# uSBasp.net
KiCad netlist of a schematic drawn in EAGLE
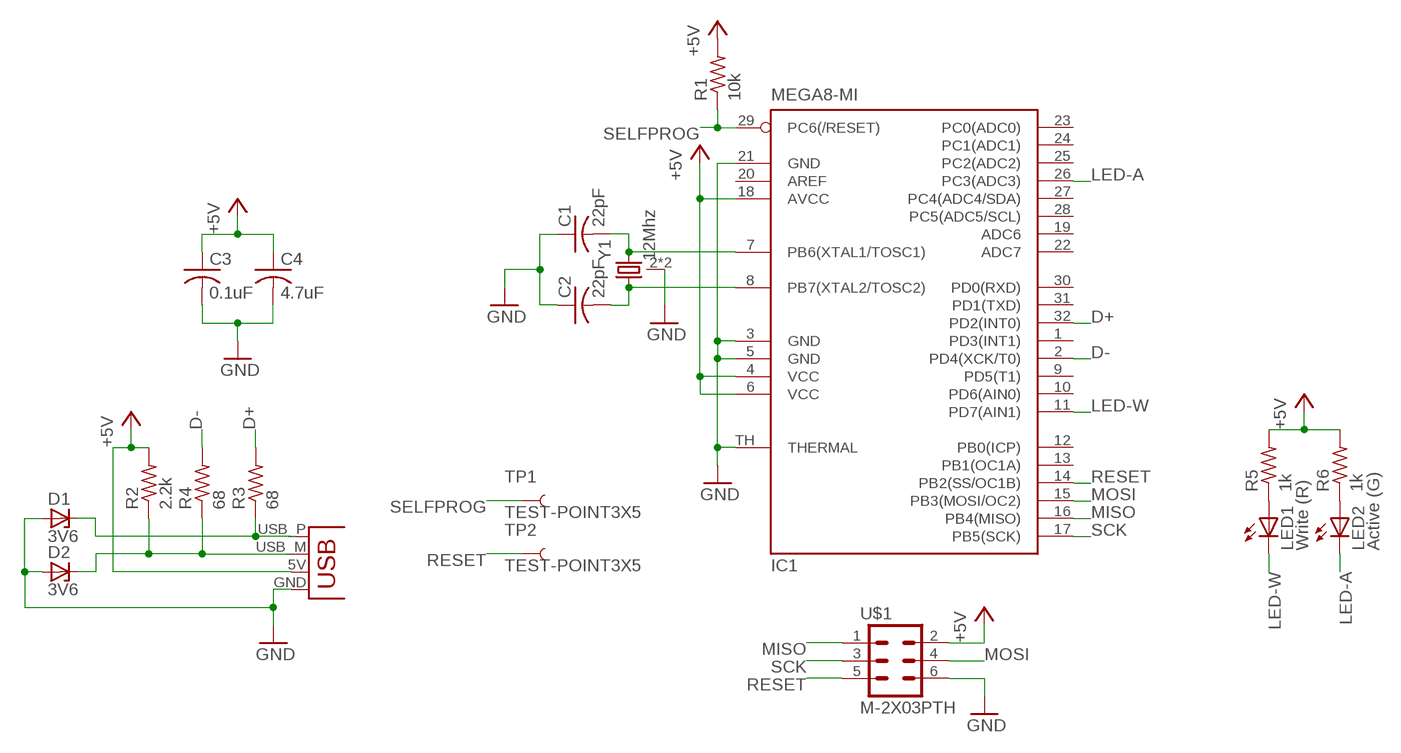
[diagram p0: schematic, sheet 1]

(export (version "E")
  (design (tool "Eeschema 10.0.6"))
  (components
    (comp (ref "C1")
      (value "22pF")
      (footprint "eagle-import:C0402")
      (libsource (lib "eagle-import") (part "C-USC0402"))
    )
    (comp (ref "C2")
      (value "22pF")
      (footprint "eagle-import:C0402")
      (libsource (lib "eagle-import") (part "C-USC0402"))
    )
    (comp (ref "C3")
      (value "0.1uF")
      (footprint "eagle-import:C0402")
      (libsource (lib "eagle-import") (part "C-USC0402"))
    )
    (comp (ref "C4")
      (value "4.7uF")
      (footprint "eagle-import:C0402")
      (libsource (lib "eagle-import") (part "C-USC0402"))
    )
    (comp (ref "D1")
      (value "3V6")
      (footprint "eagle-import:SOT23")
      (libsource (lib "eagle-import") (part "ZENER-DIODESOT23"))
    )
    (comp (ref "D2")
      (value "3V6")
      (footprint "eagle-import:SOT23")
      (libsource (lib "eagle-import") (part "ZENER-DIODESOT23"))
    )
    (comp (ref "IC1")
      (value "MEGA8-MI")
      (footprint "eagle-import:MLF32-TH")
      (fields (field (name "MPN") "ATMEGA88PA-MU"))
      (libsource (lib "eagle-import") (part "MEGA8-MI"))
    )
    (comp (ref "LED1")
      (value "Write (R)")
      (footprint "eagle-import:SML0603")
      (libsource (lib "eagle-import") (part "LEDSML0603"))
    )
    (comp (ref "LED2")
      (value "Active (G)")
      (footprint "eagle-import:SML0603")
      (libsource (lib "eagle-import") (part "LEDSML0603"))
    )
    (comp (ref "R1")
      (value "10k")
      (footprint "eagle-import:R0402")
      (libsource (lib "eagle-import") (part "R-US_R0402"))
    )
    (comp (ref "R2")
      (value "2.2k")
      (footprint "eagle-import:R0402")
      (libsource (lib "eagle-import") (part "R-US_R0402"))
    )
    (comp (ref "R3")
      (value "68")
      (footprint "eagle-import:R0402")
      (libsource (lib "eagle-import") (part "R-US_R0402"))
    )
    (comp (ref "R4")
      (value "68")
      (footprint "eagle-import:R0402")
      (libsource (lib "eagle-import") (part "R-US_R0402"))
    )
    (comp (ref "R5")
      (value "1k")
      (footprint "eagle-import:R0402")
      (libsource (lib "eagle-import") (part "R-US_R0402"))
    )
    (comp (ref "R6")
      (value "1k")
      (footprint "eagle-import:R0402")
      (libsource (lib "eagle-import") (part "R-US_R0402"))
    )
    (comp (ref "TP1")
      (value "TEST-POINT3X5")
      (footprint "eagle-import:PAD.03X.05")
      (libsource (lib "eagle-import") (part "TEST-POINT3X5"))
    )
    (comp (ref "TP2")
      (value "TEST-POINT3X5")
      (footprint "eagle-import:PAD.03X.05")
      (libsource (lib "eagle-import") (part "TEST-POINT3X5"))
    )
    (comp (ref "U$1")
      (value "M-2X03PTH")
      (footprint "eagle-import:M-2X03-0.1-PTH-EDGE")
      (libsource (lib "eagle-import") (part "M-2X03PTH"))
    )
    (comp (ref "X1")
      (value "USBPCB")
      (footprint "eagle-import:USB-A-PCB")
      (libsource (lib "eagle-import") (part "USBPCB"))
    )
    (comp (ref "Y1")
      (value "12Mhz")
      (footprint "eagle-import:CRYSTAL-SMD-3.2X2.5")
      (libsource (lib "eagle-import") (part "CRYSTAL"))
    )
  )
  (nets
    (net (code "1") (name "+5V") (class "Default")
      (node (ref "C3") (pin "1") (pinfunction "1_1") (pintype "passive"))
      (node (ref "C4") (pin "1") (pinfunction "1_1") (pintype "passive"))
      (node (ref "IC1") (pin "18") (pinfunction "AVCC_18") (pintype "power_in"))
      (node (ref "IC1") (pin "4") (pinfunction "VCC_4") (pintype "power_in"))
      (node (ref "IC1") (pin "6") (pinfunction "VCC_6") (pintype "power_in"))
      (node (ref "R1") (pin "2") (pinfunction "2_2") (pintype "passive"))
      (node (ref "R2") (pin "2") (pinfunction "2_2") (pintype "passive"))
      (node (ref "R5") (pin "2") (pinfunction "2_2") (pintype "passive"))
      (node (ref "R6") (pin "2") (pinfunction "2_2") (pintype "passive"))
      (node (ref "U$1") (pin "2") (pinfunction "2_2") (pintype "passive"))
      (node (ref "X1") (pin "5V") (pinfunction "VBUS_5V") (pintype "bidirectional"))
    )
    (net (code "2") (name "/D+") (class "Default")
      (node (ref "IC1") (pin "32") (pinfunction "PD2(INT0)_32") (pintype "bidirectional"))
      (node (ref "R3") (pin "2") (pinfunction "2_2") (pintype "passive"))
    )
    (net (code "3") (name "/D-") (class "Default")
      (node (ref "IC1") (pin "2") (pinfunction "PD4(XCK/T0)_2") (pintype "bidirectional"))
      (node (ref "R4") (pin "2") (pinfunction "2_2") (pintype "passive"))
    )
    (net (code "4") (name "/LED-A") (class "Default")
      (node (ref "IC1") (pin "26") (pinfunction "PC3(ADC3)_26") (pintype "bidirectional"))
      (node (ref "LED2") (pin "C") (pinfunction "C_C") (pintype "passive"))
    )
    (net (code "5") (name "/LED-W") (class "Default")
      (node (ref "IC1") (pin "11") (pinfunction "PD7(AIN1)_11") (pintype "bidirectional"))
      (node (ref "LED1") (pin "C") (pinfunction "C_C") (pintype "passive"))
    )
    (net (code "6") (name "/MISO") (class "Default")
      (node (ref "IC1") (pin "16") (pinfunction "PB4(MISO)_16") (pintype "bidirectional"))
      (node (ref "U$1") (pin "1") (pinfunction "1_1") (pintype "passive"))
    )
    (net (code "7") (name "/MOSI") (class "Default")
      (node (ref "IC1") (pin "15") (pinfunction "PB3(MOSI/OC2)_15") (pintype "bidirectional"))
      (node (ref "U$1") (pin "4") (pinfunction "4_4") (pintype "passive"))
    )
    (net (code "8") (name "/RESET") (class "Default")
      (node (ref "IC1") (pin "14") (pinfunction "PB2(SS/OC1B)_14") (pintype "bidirectional"))
      (node (ref "TP2") (pin "P$1") (pinfunction "1_P$1") (pintype "bidirectional"))
      (node (ref "U$1") (pin "5") (pinfunction "5_5") (pintype "passive"))
    )
    (net (code "9") (name "/SCK") (class "Default")
      (node (ref "IC1") (pin "17") (pinfunction "PB5(SCK)_17") (pintype "bidirectional"))
      (node (ref "U$1") (pin "3") (pinfunction "3_3") (pintype "passive"))
    )
    (net (code "10") (name "/SELFPROG") (class "Default")
      (node (ref "IC1") (pin "29") (pinfunction "PC6(/RESET)_29") (pintype "bidirectional"))
      (node (ref "R1") (pin "1") (pinfunction "1_1") (pintype "passive"))
      (node (ref "TP1") (pin "P$1") (pinfunction "1_P$1") (pintype "bidirectional"))
    )
    (net (code "11") (name "GND") (class "Default")
      (node (ref "C1") (pin "1") (pinfunction "1_1") (pintype "passive"))
      (node (ref "C2") (pin "1") (pinfunction "1_1") (pintype "passive"))
      (node (ref "C3") (pin "2") (pinfunction "2_2") (pintype "passive"))
      (node (ref "C4") (pin "2") (pinfunction "2_2") (pintype "passive"))
      (node (ref "D1") (pin "1") (pinfunction "A_1") (pintype "passive"))
      (node (ref "D2") (pin "1") (pinfunction "A_1") (pintype "passive"))
      (node (ref "IC1") (pin "21") (pinfunction "GND_21") (pintype "power_in"))
      (node (ref "IC1") (pin "3") (pinfunction "GND_3") (pintype "power_in"))
      (node (ref "IC1") (pin "5") (pinfunction "GND_5") (pintype "power_in"))
      (node (ref "IC1") (pin "TH") (pinfunction "THERMAL_TH") (pintype "passive"))
      (node (ref "U$1") (pin "6") (pinfunction "6_6") (pintype "passive"))
      (node (ref "X1") (pin "GND") (pinfunction "GND_GND") (pintype "bidirectional"))
      (node (ref "Y1") (pin "2") (pinfunction "GND_2") (pintype "passive"))
      (node (ref "Y1") (pin "4") (pinfunction "GND_4") (pintype "passive"))
    )
    (net (code "12") (name "Net-(D1-C)") (class "Default")
      (node (ref "D1") (pin "3") (pinfunction "C_3") (pintype "passive"))
      (node (ref "R3") (pin "1") (pinfunction "1_1") (pintype "passive"))
      (node (ref "X1") (pin "USB_P") (pinfunction "D+_USB_P") (pintype "bidirectional"))
    )
    (net (code "13") (name "Net-(D2-C)") (class "Default")
      (node (ref "D2") (pin "3") (pinfunction "C_3") (pintype "passive"))
      (node (ref "R2") (pin "1") (pinfunction "1_1") (pintype "passive"))
      (node (ref "R4") (pin "1") (pinfunction "1_1") (pintype "passive"))
      (node (ref "X1") (pin "USB_M") (pinfunction "D-_USB_M") (pintype "bidirectional"))
    )
    (net (code "14") (name "Net-(IC1-PB6(XTAL1{slash}TOSC1))") (class "Default")
      (node (ref "C1") (pin "2") (pinfunction "2_2") (pintype "passive"))
      (node (ref "IC1") (pin "7") (pinfunction "PB6(XTAL1/TOSC1)_7") (pintype "bidirectional"))
      (node (ref "Y1") (pin "3") (pinfunction "2_3") (pintype "passive"))
    )
    (net (code "15") (name "Net-(IC1-PB7(XTAL2{slash}TOSC2))") (class "Default")
      (node (ref "C2") (pin "2") (pinfunction "2_2") (pintype "passive"))
      (node (ref "IC1") (pin "8") (pinfunction "PB7(XTAL2/TOSC2)_8") (pintype "bidirectional"))
      (node (ref "Y1") (pin "1") (pinfunction "1_1") (pintype "passive"))
    )
    (net (code "16") (name "Net-(LED1-PadA)") (class "Default")
      (node (ref "LED1") (pin "A") (pinfunction "A_A") (pintype "passive"))
      (node (ref "R5") (pin "1") (pinfunction "1_1") (pintype "passive"))
    )
    (net (code "17") (name "Net-(LED2-PadA)") (class "Default")
      (node (ref "LED2") (pin "A") (pinfunction "A_A") (pintype "passive"))
      (node (ref "R6") (pin "1") (pinfunction "1_1") (pintype "passive"))
    )
    (net (code "18") (name "unconnected-(IC1-ADC6-Pad19)") (class "Default")
      (node (ref "IC1") (pin "19") (pinfunction "ADC6_19") (pintype "bidirectional"))
    )
    (net (code "19") (name "unconnected-(IC1-ADC7-Pad22)") (class "Default")
      (node (ref "IC1") (pin "22") (pinfunction "ADC7_22") (pintype "bidirectional"))
    )
    (net (code "20") (name "unconnected-(IC1-AREF-Pad20)") (class "Default")
      (node (ref "IC1") (pin "20") (pinfunction "AREF_20") (pintype "passive"))
    )
    (net (code "21") (name "unconnected-(IC1-PB0(ICP)-Pad12)") (class "Default")
      (node (ref "IC1") (pin "12") (pinfunction "PB0(ICP)_12") (pintype "bidirectional"))
    )
    (net (code "22") (name "unconnected-(IC1-PB1(OC1A)-Pad13)") (class "Default")
      (node (ref "IC1") (pin "13") (pinfunction "PB1(OC1A)_13") (pintype "bidirectional"))
    )
    (net (code "23") (name "unconnected-(IC1-PC0(ADC0)-Pad23)") (class "Default")
      (node (ref "IC1") (pin "23") (pinfunction "PC0(ADC0)_23") (pintype "bidirectional"))
    )
    (net (code "24") (name "unconnected-(IC1-PC1(ADC1)-Pad24)") (class "Default")
      (node (ref "IC1") (pin "24") (pinfunction "PC1(ADC1)_24") (pintype "bidirectional"))
    )
    (net (code "25") (name "unconnected-(IC1-PC2(ADC2)-Pad25)") (class "Default")
      (node (ref "IC1") (pin "25") (pinfunction "PC2(ADC2)_25") (pintype "bidirectional"))
    )
    (net (code "26") (name "unconnected-(IC1-PC4(ADC4{slash}SDA)-Pad27)") (class "Default")
      (node (ref "IC1") (pin "27") (pinfunction "PC4(ADC4/SDA)_27") (pintype "bidirectional"))
    )
    (net (code "27") (name "unconnected-(IC1-PC5(ADC5{slash}SCL)-Pad28)") (class "Default")
      (node (ref "IC1") (pin "28") (pinfunction "PC5(ADC5/SCL)_28") (pintype "bidirectional"))
    )
    (net (code "28") (name "unconnected-(IC1-PD0(RXD)-Pad30)") (class "Default")
      (node (ref "IC1") (pin "30") (pinfunction "PD0(RXD)_30") (pintype "bidirectional"))
    )
    (net (code "29") (name "unconnected-(IC1-PD1(TXD)-Pad31)") (class "Default")
      (node (ref "IC1") (pin "31") (pinfunction "PD1(TXD)_31") (pintype "bidirectional"))
    )
    (net (code "30") (name "unconnected-(IC1-PD3(INT1)-Pad1)") (class "Default")
      (node (ref "IC1") (pin "1") (pinfunction "PD3(INT1)_1") (pintype "bidirectional"))
    )
    (net (code "31") (name "unconnected-(IC1-PD5(T1)-Pad9)") (class "Default")
      (node (ref "IC1") (pin "9") (pinfunction "PD5(T1)_9") (pintype "bidirectional"))
    )
    (net (code "32") (name "unconnected-(IC1-PD6(AIN0)-Pad10)") (class "Default")
      (node (ref "IC1") (pin "10") (pinfunction "PD6(AIN0)_10") (pintype "bidirectional"))
    )
  )
)
